# LSM330DLC.net
KiCad netlist of a schematic drawn in EAGLE
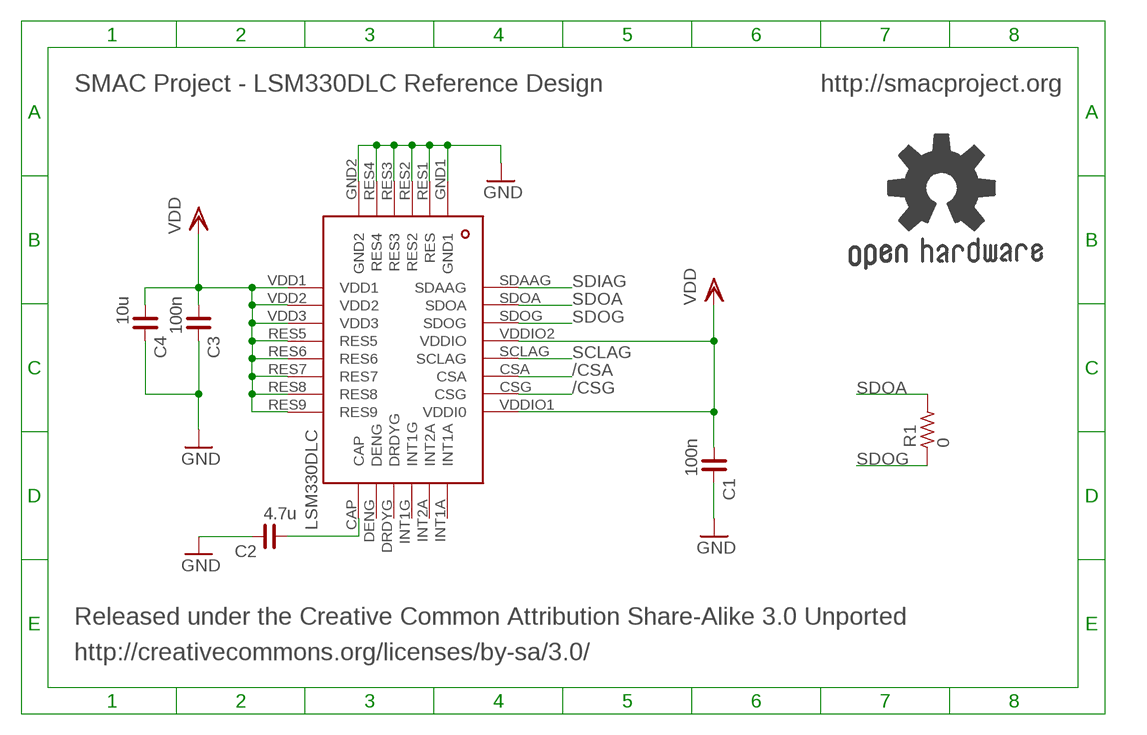
[diagram p0: schematic, sheet 1]

(export (version "E")
  (design (tool "Eeschema 10.0.6"))
  (components
    (comp (ref "C1")
      (value "100n")
      (footprint "eagle-import:C0402")
      (libsource (lib "eagle-import") (part "C_0402"))
    )
    (comp (ref "C2")
      (value "4.7u")
      (footprint "eagle-import:C0402")
      (libsource (lib "eagle-import") (part "C_0402"))
    )
    (comp (ref "C3")
      (value "100n")
      (footprint "eagle-import:C0402")
      (libsource (lib "eagle-import") (part "C_0402"))
    )
    (comp (ref "C4")
      (value "10u")
      (footprint "eagle-import:C0402")
      (libsource (lib "eagle-import") (part "C_0402"))
    )
    (comp (ref "GOLD_ORB_SM2")
      (value "OSHWLOGO_REF_SM")
      (footprint "eagle-import:OSHW2REF")
      (libsource (lib "eagle-import") (part "OSHWLOGO_REF_SM"))
    )
    (comp (ref "IC1")
      (value "LSM330DLC")
      (footprint "eagle-import:LSM330DLC")
      (libsource (lib "eagle-import") (part "LSM330DLC"))
    )
    (comp (ref "R1")
      (value "0")
      (footprint "eagle-import:R0402")
      (libsource (lib "eagle-import") (part "R_0402"))
    )
  )
  (nets
    (net (code "1") (name "/SCLAG") (class "Default")
      (node (ref "IC1") (pin "SCLAG") (pinfunction "SCLAG_SCLAG") (pintype "input"))
    )
    (net (code "2") (name "/SDIAG") (class "Default")
      (node (ref "IC1") (pin "SDAAG") (pinfunction "SDAAG_SDAAG") (pintype "bidirectional"))
    )
    (net (code "3") (name "/SDOA") (class "Default")
      (node (ref "IC1") (pin "SDOA") (pinfunction "SDOA_SDOA") (pintype "bidirectional"))
      (node (ref "R1") (pin "2") (pinfunction "2_2") (pintype "passive"))
    )
    (net (code "4") (name "/SDOG") (class "Default")
      (node (ref "IC1") (pin "SDOG") (pinfunction "SDOG_SDOG") (pintype "bidirectional"))
      (node (ref "R1") (pin "1") (pinfunction "1_1") (pintype "passive"))
    )
    (net (code "5") (name "/{slash}CSA") (class "Default")
      (node (ref "IC1") (pin "CSA") (pinfunction "CSA_CSA") (pintype "input"))
    )
    (net (code "6") (name "/{slash}CSG") (class "Default")
      (node (ref "IC1") (pin "CSG") (pinfunction "CSG_CSG") (pintype "input"))
    )
    (net (code "7") (name "GND") (class "Default")
      (node (ref "C1") (pin "2") (pinfunction "2_2") (pintype "passive"))
      (node (ref "C2") (pin "2") (pinfunction "2_2") (pintype "passive"))
      (node (ref "C3") (pin "2") (pinfunction "2_2") (pintype "passive"))
      (node (ref "C4") (pin "2") (pinfunction "2_2") (pintype "passive"))
      (node (ref "IC1") (pin "GND1") (pinfunction "GND1_GND1") (pintype "power_in"))
      (node (ref "IC1") (pin "GND2") (pinfunction "GND2_GND2") (pintype "power_in"))
      (node (ref "IC1") (pin "RES1") (pinfunction "RES_RES1") (pintype "power_in"))
      (node (ref "IC1") (pin "RES2") (pinfunction "RES2_RES2") (pintype "power_in"))
      (node (ref "IC1") (pin "RES3") (pinfunction "RES3_RES3") (pintype "bidirectional"))
      (node (ref "IC1") (pin "RES4") (pinfunction "RES4_RES4") (pintype "bidirectional"))
    )
    (net (code "8") (name "Net-(C2-Pad1)") (class "Default")
      (node (ref "C2") (pin "1") (pinfunction "1_1") (pintype "passive"))
      (node (ref "IC1") (pin "CAP") (pinfunction "CAP_CAP") (pintype "passive"))
    )
    (net (code "9") (name "VDD") (class "Default")
      (node (ref "C1") (pin "1") (pinfunction "1_1") (pintype "passive"))
      (node (ref "C3") (pin "1") (pinfunction "1_1") (pintype "passive"))
      (node (ref "C4") (pin "1") (pinfunction "1_1") (pintype "passive"))
      (node (ref "IC1") (pin "RES5") (pinfunction "RES5_RES5") (pintype "bidirectional"))
      (node (ref "IC1") (pin "RES6") (pinfunction "RES6_RES6") (pintype "bidirectional"))
      (node (ref "IC1") (pin "RES7") (pinfunction "RES7_RES7") (pintype "bidirectional"))
      (node (ref "IC1") (pin "RES8") (pinfunction "RES8_RES8") (pintype "bidirectional"))
      (node (ref "IC1") (pin "RES9") (pinfunction "RES9_RES9") (pintype "bidirectional"))
      (node (ref "IC1") (pin "VDD1") (pinfunction "VDD1_VDD1") (pintype "power_in"))
      (node (ref "IC1") (pin "VDD2") (pinfunction "VDD2_VDD2") (pintype "power_in"))
      (node (ref "IC1") (pin "VDD3") (pinfunction "VDD3_VDD3") (pintype "power_in"))
      (node (ref "IC1") (pin "VDDIO1") (pinfunction "VDDI0_VDDIO1") (pintype "power_in"))
      (node (ref "IC1") (pin "VDDIO2") (pinfunction "VDDIO_VDDIO2") (pintype "power_in"))
    )
    (net (code "10") (name "unconnected-(IC1-PadDENG)") (class "Default")
      (node (ref "IC1") (pin "DENG") (pinfunction "DENG_DENG") (pintype "input"))
    )
    (net (code "11") (name "unconnected-(IC1-PadDRDYG)") (class "Default")
      (node (ref "IC1") (pin "DRDYG") (pinfunction "DRDYG_DRDYG") (pintype "output"))
    )
    (net (code "12") (name "unconnected-(IC1-PadINT1A)") (class "Default")
      (node (ref "IC1") (pin "INT1A") (pinfunction "INT1A_INT1A") (pintype "output"))
    )
    (net (code "13") (name "unconnected-(IC1-PadINT1G)") (class "Default")
      (node (ref "IC1") (pin "INT1G") (pinfunction "INT1G_INT1G") (pintype "output"))
    )
    (net (code "14") (name "unconnected-(IC1-PadINT2A)") (class "Default")
      (node (ref "IC1") (pin "INT2A") (pinfunction "INT2A_INT2A") (pintype "output"))
    )
  )
)
